# design.net
KiCad netlist of a schematic drawn in EAGLE
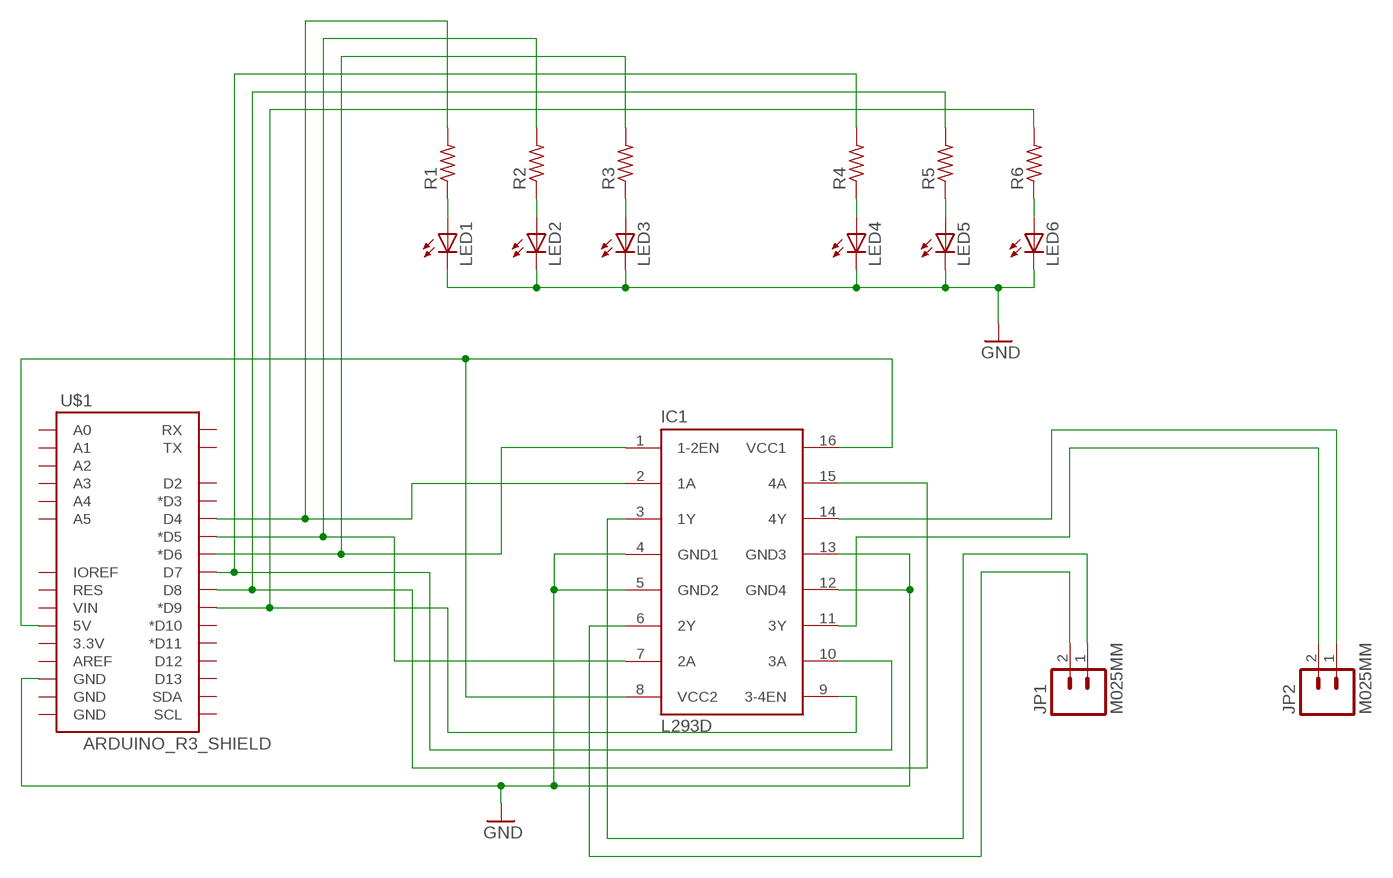
[diagram p0: schematic, sheet 1]

(export (version "E")
  (design (tool "Eeschema 10.0.6"))
  (components
    (comp (ref "IC1")
      (value "L293D")
      (footprint "eagle-import:DIL16")
      (libsource (lib "eagle-import") (part "L293D"))
    )
    (comp (ref "JP1")
      (value "M025MM")
      (footprint "eagle-import:SCREWTERMINAL-5MM-2")
      (libsource (lib "eagle-import") (part "M025MM"))
    )
    (comp (ref "JP2")
      (value "M025MM")
      (footprint "eagle-import:SCREWTERMINAL-5MM-2")
      (libsource (lib "eagle-import") (part "M025MM"))
    )
    (comp (ref "LED1")
      (value "LED5MM")
      (footprint "eagle-import:LED5MM")
      (libsource (lib "eagle-import") (part "LED5MM"))
    )
    (comp (ref "LED2")
      (value "LED5MM")
      (footprint "eagle-import:LED5MM")
      (libsource (lib "eagle-import") (part "LED5MM"))
    )
    (comp (ref "LED3")
      (value "LED5MM")
      (footprint "eagle-import:LED5MM")
      (libsource (lib "eagle-import") (part "LED5MM"))
    )
    (comp (ref "LED4")
      (value "LED5MM")
      (footprint "eagle-import:LED5MM")
      (libsource (lib "eagle-import") (part "LED5MM"))
    )
    (comp (ref "LED5")
      (value "LED5MM")
      (footprint "eagle-import:LED5MM")
      (libsource (lib "eagle-import") (part "LED5MM"))
    )
    (comp (ref "LED6")
      (value "LED5MM")
      (footprint "eagle-import:LED5MM")
      (libsource (lib "eagle-import") (part "LED5MM"))
    )
    (comp (ref "R1")
      (value "R-US_0207/9")
      (footprint "eagle-import:0207_9")
      (libsource (lib "eagle-import") (part "R-US_0207/9"))
    )
    (comp (ref "R2")
      (value "R-US_0207/9")
      (footprint "eagle-import:0207_9")
      (libsource (lib "eagle-import") (part "R-US_0207/9"))
    )
    (comp (ref "R3")
      (value "R-US_0207/9")
      (footprint "eagle-import:0207_9")
      (libsource (lib "eagle-import") (part "R-US_0207/9"))
    )
    (comp (ref "R4")
      (value "R-US_0207/9")
      (footprint "eagle-import:0207_9")
      (libsource (lib "eagle-import") (part "R-US_0207/9"))
    )
    (comp (ref "R5")
      (value "R-US_0207/9")
      (footprint "eagle-import:0207_9")
      (libsource (lib "eagle-import") (part "R-US_0207/9"))
    )
    (comp (ref "R6")
      (value "R-US_0207/9")
      (footprint "eagle-import:0207_9")
      (libsource (lib "eagle-import") (part "R-US_0207/9"))
    )
    (comp (ref "U$1")
      (value "ARDUINO_R3_SHIELD")
      (footprint "eagle-import:UNO_R3_SHIELD")
      (libsource (lib "eagle-import") (part "ARDUINO_R3_SHIELD"))
    )
  )
  (nets
    (net (code "1") (name "GND") (class "Default")
      (node (ref "IC1") (pin "12") (pinfunction "GND4_12") (pintype "power_in"))
      (node (ref "IC1") (pin "13") (pinfunction "GND3_13") (pintype "power_in"))
      (node (ref "IC1") (pin "4") (pinfunction "GND1_4") (pintype "power_in"))
      (node (ref "IC1") (pin "5") (pinfunction "GND2_5") (pintype "power_in"))
      (node (ref "LED1") (pin "K") (pinfunction "C_K") (pintype "passive"))
      (node (ref "LED2") (pin "K") (pinfunction "C_K") (pintype "passive"))
      (node (ref "LED3") (pin "K") (pinfunction "C_K") (pintype "passive"))
      (node (ref "LED4") (pin "K") (pinfunction "C_K") (pintype "passive"))
      (node (ref "LED5") (pin "K") (pinfunction "C_K") (pintype "passive"))
      (node (ref "LED6") (pin "K") (pinfunction "C_K") (pintype "passive"))
      (node (ref "U$1") (pin "GND@2") (pinfunction "GND_GND@2") (pintype "bidirectional"))
    )
    (net (code "2") (name "Net-(IC1-1-2EN)") (class "Default")
      (node (ref "IC1") (pin "1") (pinfunction "1-2EN_1") (pintype "input"))
      (node (ref "R3") (pin "2") (pinfunction "2_2") (pintype "passive"))
      (node (ref "U$1") (pin "D6") (pinfunction "*D6_D6") (pintype "bidirectional"))
    )
    (net (code "3") (name "Net-(IC1-1A)") (class "Default")
      (node (ref "IC1") (pin "2") (pinfunction "1A_2") (pintype "input"))
      (node (ref "R1") (pin "2") (pinfunction "2_2") (pintype "passive"))
      (node (ref "U$1") (pin "D4") (pinfunction "D4_D4") (pintype "bidirectional"))
    )
    (net (code "4") (name "Net-(IC1-1Y)") (class "Default")
      (node (ref "IC1") (pin "3") (pinfunction "1Y_3") (pintype "output"))
      (node (ref "JP1") (pin "1") (pinfunction "1_1") (pintype "passive"))
    )
    (net (code "5") (name "Net-(IC1-2A)") (class "Default")
      (node (ref "IC1") (pin "7") (pinfunction "2A_7") (pintype "input"))
      (node (ref "R2") (pin "2") (pinfunction "2_2") (pintype "passive"))
      (node (ref "U$1") (pin "D5") (pinfunction "*D5_D5") (pintype "bidirectional"))
    )
    (net (code "6") (name "Net-(IC1-2Y)") (class "Default")
      (node (ref "IC1") (pin "6") (pinfunction "2Y_6") (pintype "output"))
      (node (ref "JP1") (pin "2") (pinfunction "2_2") (pintype "passive"))
    )
    (net (code "7") (name "Net-(IC1-3-4EN)") (class "Default")
      (node (ref "IC1") (pin "9") (pinfunction "3-4EN_9") (pintype "input"))
      (node (ref "R6") (pin "2") (pinfunction "2_2") (pintype "passive"))
      (node (ref "U$1") (pin "D9") (pinfunction "*D9_D9") (pintype "bidirectional"))
    )
    (net (code "8") (name "Net-(IC1-3A)") (class "Default")
      (node (ref "IC1") (pin "10") (pinfunction "3A_10") (pintype "input"))
      (node (ref "R4") (pin "2") (pinfunction "2_2") (pintype "passive"))
      (node (ref "U$1") (pin "D7") (pinfunction "D7_D7") (pintype "bidirectional"))
    )
    (net (code "9") (name "Net-(IC1-3Y)") (class "Default")
      (node (ref "IC1") (pin "11") (pinfunction "3Y_11") (pintype "output"))
      (node (ref "JP2") (pin "2") (pinfunction "2_2") (pintype "passive"))
    )
    (net (code "10") (name "Net-(IC1-4A)") (class "Default")
      (node (ref "IC1") (pin "15") (pinfunction "4A_15") (pintype "input"))
      (node (ref "R5") (pin "2") (pinfunction "2_2") (pintype "passive"))
      (node (ref "U$1") (pin "D8") (pinfunction "D8_D8") (pintype "bidirectional"))
    )
    (net (code "11") (name "Net-(IC1-4Y)") (class "Default")
      (node (ref "IC1") (pin "14") (pinfunction "4Y_14") (pintype "output"))
      (node (ref "JP2") (pin "1") (pinfunction "1_1") (pintype "passive"))
    )
    (net (code "12") (name "Net-(IC1-VCC1)") (class "Default")
      (node (ref "IC1") (pin "16") (pinfunction "VCC1_16") (pintype "power_in"))
      (node (ref "IC1") (pin "8") (pinfunction "VCC2_8") (pintype "power_in"))
      (node (ref "U$1") (pin "5V") (pinfunction "5V_5V") (pintype "bidirectional"))
    )
    (net (code "13") (name "Net-(LED1-PadA)") (class "Default")
      (node (ref "LED1") (pin "A") (pinfunction "A_A") (pintype "passive"))
      (node (ref "R1") (pin "1") (pinfunction "1_1") (pintype "passive"))
    )
    (net (code "14") (name "Net-(LED2-PadA)") (class "Default")
      (node (ref "LED2") (pin "A") (pinfunction "A_A") (pintype "passive"))
      (node (ref "R2") (pin "1") (pinfunction "1_1") (pintype "passive"))
    )
    (net (code "15") (name "Net-(LED3-PadA)") (class "Default")
      (node (ref "LED3") (pin "A") (pinfunction "A_A") (pintype "passive"))
      (node (ref "R3") (pin "1") (pinfunction "1_1") (pintype "passive"))
    )
    (net (code "16") (name "Net-(LED4-PadA)") (class "Default")
      (node (ref "LED4") (pin "A") (pinfunction "A_A") (pintype "passive"))
      (node (ref "R4") (pin "1") (pinfunction "1_1") (pintype "passive"))
    )
    (net (code "17") (name "Net-(LED5-PadA)") (class "Default")
      (node (ref "LED5") (pin "A") (pinfunction "A_A") (pintype "passive"))
      (node (ref "R5") (pin "1") (pinfunction "1_1") (pintype "passive"))
    )
    (net (code "18") (name "Net-(LED6-PadA)") (class "Default")
      (node (ref "LED6") (pin "A") (pinfunction "A_A") (pintype "passive"))
      (node (ref "R6") (pin "1") (pinfunction "1_1") (pintype "passive"))
    )
    (net (code "19") (name "unconnected-(U$1-*D3-PadD3)") (class "Default")
      (node (ref "U$1") (pin "D3") (pinfunction "*D3_D3") (pintype "bidirectional"))
    )
    (net (code "20") (name "unconnected-(U$1-*D10-PadD10)") (class "Default")
      (node (ref "U$1") (pin "D10") (pinfunction "*D10_D10") (pintype "bidirectional"))
    )
    (net (code "21") (name "unconnected-(U$1-*D11-PadD11)") (class "Default")
      (node (ref "U$1") (pin "D11") (pinfunction "*D11_D11") (pintype "bidirectional"))
    )
    (net (code "22") (name "unconnected-(U$1-GND-PadGND@0)") (class "Default")
      (node (ref "U$1") (pin "GND@0") (pinfunction "GND_GND@0") (pintype "bidirectional"))
    )
    (net (code "23") (name "unconnected-(U$1-GND-PadGND@1)") (class "Default")
      (node (ref "U$1") (pin "GND@1") (pinfunction "GND_GND@1") (pintype "bidirectional"))
    )
    (net (code "24") (name "unconnected-(U$1-Pad3.3V)") (class "Default")
      (node (ref "U$1") (pin "3.3V") (pinfunction "3.3V_3.3V") (pintype "bidirectional"))
    )
    (net (code "25") (name "unconnected-(U$1-PadA0)") (class "Default")
      (node (ref "U$1") (pin "A0") (pinfunction "A0_A0") (pintype "bidirectional"))
    )
    (net (code "26") (name "unconnected-(U$1-PadA1)") (class "Default")
      (node (ref "U$1") (pin "A1") (pinfunction "A1_A1") (pintype "bidirectional"))
    )
    (net (code "27") (name "unconnected-(U$1-PadA2)") (class "Default")
      (node (ref "U$1") (pin "A2") (pinfunction "A2_A2") (pintype "bidirectional"))
    )
    (net (code "28") (name "unconnected-(U$1-PadA3)") (class "Default")
      (node (ref "U$1") (pin "A3") (pinfunction "A3_A3") (pintype "bidirectional"))
    )
    (net (code "29") (name "unconnected-(U$1-PadA4)") (class "Default")
      (node (ref "U$1") (pin "A4") (pinfunction "A4_A4") (pintype "bidirectional"))
    )
    (net (code "30") (name "unconnected-(U$1-PadA5)") (class "Default")
      (node (ref "U$1") (pin "A5") (pinfunction "A5_A5") (pintype "bidirectional"))
    )
    (net (code "31") (name "unconnected-(U$1-PadAREF)") (class "Default")
      (node (ref "U$1") (pin "AREF") (pinfunction "AREF_AREF") (pintype "bidirectional"))
    )
    (net (code "32") (name "unconnected-(U$1-PadD2)") (class "Default")
      (node (ref "U$1") (pin "D2") (pinfunction "D2_D2") (pintype "bidirectional"))
    )
    (net (code "33") (name "unconnected-(U$1-PadD12)") (class "Default")
      (node (ref "U$1") (pin "D12") (pinfunction "D12_D12") (pintype "bidirectional"))
    )
    (net (code "34") (name "unconnected-(U$1-PadD13)") (class "Default")
      (node (ref "U$1") (pin "D13") (pinfunction "D13_D13") (pintype "bidirectional"))
    )
    (net (code "35") (name "unconnected-(U$1-PadIOREF)") (class "Default")
      (node (ref "U$1") (pin "IOREF") (pinfunction "IOREF_IOREF") (pintype "bidirectional"))
    )
    (net (code "36") (name "unconnected-(U$1-PadRES)") (class "Default")
      (node (ref "U$1") (pin "RES") (pinfunction "RES_RES") (pintype "bidirectional"))
    )
    (net (code "37") (name "unconnected-(U$1-PadRX)") (class "Default")
      (node (ref "U$1") (pin "RX") (pinfunction "RX_RX") (pintype "bidirectional"))
    )
    (net (code "38") (name "unconnected-(U$1-PadSCL)") (class "Default")
      (node (ref "U$1") (pin "SCL") (pinfunction "SCL_SCL") (pintype "bidirectional"))
    )
    (net (code "39") (name "unconnected-(U$1-PadSDA)") (class "Default")
      (node (ref "U$1") (pin "SDA") (pinfunction "SDA_SDA") (pintype "bidirectional"))
    )
    (net (code "40") (name "unconnected-(U$1-PadTX)") (class "Default")
      (node (ref "U$1") (pin "TX") (pinfunction "TX_TX") (pintype "bidirectional"))
    )
    (net (code "41") (name "unconnected-(U$1-PadVIN)") (class "Default")
      (node (ref "U$1") (pin "VIN") (pinfunction "VIN_VIN") (pintype "bidirectional"))
    )
  )
)
